# SolenoidSwitching.net
KiCad netlist of a schematic drawn in Altium Designer
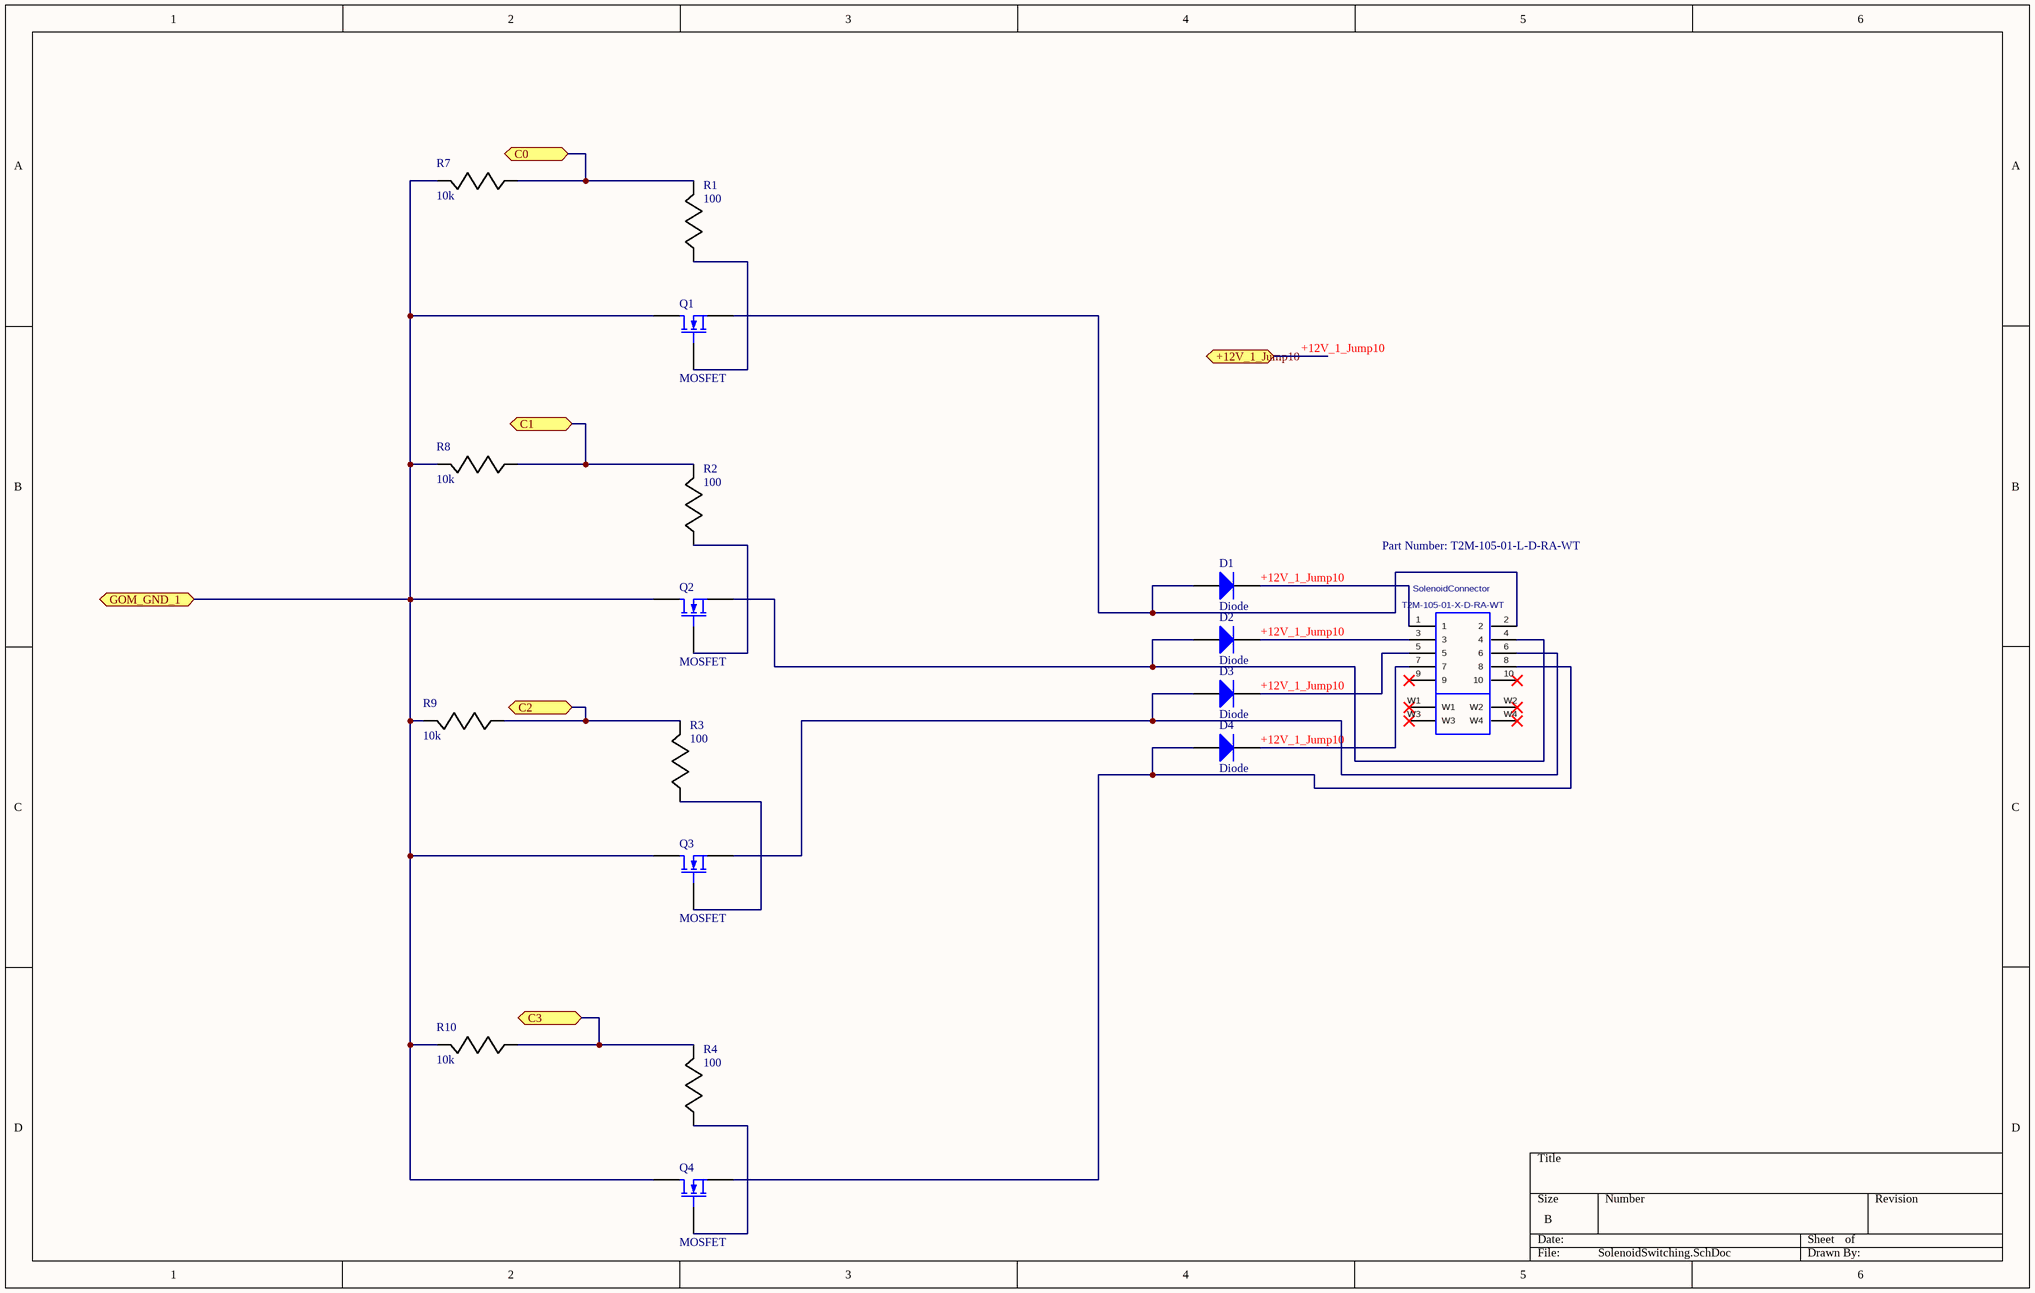
[diagram p0: SolenoidSwitching.SchDoc]

(export (version "E")
  (design (tool "Eeschema 10.0.6"))
  (components
    (comp (ref "D1")
      (value "Diode")
      (footprint "SMC")
      (description "Default Diode")
      (fields (field (name "PUBLISHER") "Altium Limited"))
      (libsource (lib "Miscellaneous Devices") (part "Diode"))
    )
    (comp (ref "D2")
      (value "Diode")
      (footprint "SMC")
      (description "Default Diode")
      (fields (field (name "PUBLISHER") "Altium Limited"))
      (libsource (lib "Miscellaneous Devices") (part "Diode"))
    )
    (comp (ref "D3")
      (value "Diode")
      (footprint "SMC")
      (description "Default Diode")
      (fields (field (name "PUBLISHER") "Altium Limited"))
      (libsource (lib "Miscellaneous Devices") (part "Diode"))
    )
    (comp (ref "D4")
      (value "Diode")
      (footprint "SMC")
      (description "Default Diode")
      (fields (field (name "PUBLISHER") "Altium Limited"))
      (libsource (lib "Miscellaneous Devices") (part "Diode"))
    )
    (comp (ref "Q1")
      (value "MOSFET")
      (footprint "TO-226-AA")
      (description "N-Channel MOSFET")
      (fields (field (name "PUBLISHER") "Altium Limited"))
      (libsource (lib "Miscellaneous Devices") (part "MOSFET-N"))
    )
    (comp (ref "Q2")
      (value "MOSFET")
      (footprint "TO-226-AA")
      (description "N-Channel MOSFET")
      (fields (field (name "PUBLISHER") "Altium Limited"))
      (libsource (lib "Miscellaneous Devices") (part "MOSFET-N"))
    )
    (comp (ref "Q3")
      (value "MOSFET")
      (footprint "TO-226-AA")
      (description "N-Channel MOSFET")
      (fields (field (name "PUBLISHER") "Altium Limited"))
      (libsource (lib "Miscellaneous Devices") (part "MOSFET-N"))
    )
    (comp (ref "Q4")
      (value "MOSFET")
      (footprint "TO-226-AA")
      (description "N-Channel MOSFET")
      (fields (field (name "PUBLISHER") "Altium Limited"))
      (libsource (lib "Miscellaneous Devices") (part "MOSFET-N"))
    )
    (comp (ref "R1")
      (value "100")
      (footprint "AXIAL-0.3")
      (description "Imported")
      (fields (field (name "MANUFACTURER_PART_NUMBER") "PMR100HZPFU6L00"))
      (libsource (lib "2016-03-26_18-23-46") (part "PMR100HZPFU6L00"))
    )
    (comp (ref "R2")
      (value "100")
      (footprint "AXIAL-0.3")
      (description "Imported")
      (fields (field (name "MANUFACTURER_PART_NUMBER") "PMR100HZPFU6L00"))
      (libsource (lib "2016-03-26_18-23-46") (part "PMR100HZPFU6L00"))
    )
    (comp (ref "R3")
      (value "100")
      (footprint "AXIAL-0.3")
      (description "Imported")
      (fields (field (name "MANUFACTURER_PART_NUMBER") "PMR100HZPFU6L00"))
      (libsource (lib "2016-03-26_18-23-46") (part "PMR100HZPFU6L00"))
    )
    (comp (ref "R4")
      (value "100")
      (footprint "AXIAL-0.3")
      (description "Imported")
      (fields (field (name "MANUFACTURER_PART_NUMBER") "PMR100HZPFU6L00"))
      (libsource (lib "2016-03-26_18-23-46") (part "PMR100HZPFU6L00"))
    )
    (comp (ref "R7")
      (value "10k")
      (footprint "AXIAL-0.3")
      (description "Imported")
      (fields (field (name "MANUFACTURER_PART_NUMBER") "PMR100HZPFU6L00"))
      (libsource (lib "2016-03-26_18-23-46") (part "PMR100HZPFU6L00"))
    )
    (comp (ref "R8")
      (value "10k")
      (footprint "AXIAL-0.3")
      (description "Imported")
      (fields (field (name "MANUFACTURER_PART_NUMBER") "PMR100HZPFU6L00"))
      (libsource (lib "2016-03-26_18-23-46") (part "PMR100HZPFU6L00"))
    )
    (comp (ref "R9")
      (value "10k")
      (footprint "AXIAL-0.3")
      (description "Imported")
      (fields (field (name "MANUFACTURER_PART_NUMBER") "PMR100HZPFU6L00"))
      (libsource (lib "2016-03-26_18-23-46") (part "PMR100HZPFU6L00"))
    )
    (comp (ref "R10")
      (value "10k")
      (footprint "AXIAL-0.3")
      (description "Imported")
      (fields (field (name "MANUFACTURER_PART_NUMBER") "PMR100HZPFU6L00"))
      (libsource (lib "2016-03-26_18-23-46") (part "PMR100HZPFU6L00"))
    )
    (comp (ref "SolenoidConnector")
      (value "T2M-105-01-X-D-RA-WT")
      (footprint "T2M-105-01-X-D-RA-WT")
      (description "2MM PITCH SHROUDED RIGHT ANGLE TERMINAL STRIP.")
      (fields
        (field (name "MANUFACTURER") "SAMTEC")
        (field (name "CREATED") "September 24, 2014 - Wendy Xin")
      )
      (libsource (lib "T2M-105-01-X-D-RA-WT") (part "T2M-105-01-X-D-RA-WT"))
    )
  )
  (nets
    (net (code "1") (name "/+12V_1_Jump10") (class "Default")
      (node (ref "D1") (pin "2") (pinfunction "K_2") (pintype "passive"))
      (node (ref "D2") (pin "2") (pinfunction "K_2") (pintype "passive"))
      (node (ref "D3") (pin "2") (pinfunction "K_2") (pintype "passive"))
      (node (ref "D4") (pin "2") (pinfunction "K_2") (pintype "passive"))
      (node (ref "SolenoidConnector") (pin "1") (pinfunction "1_1") (pintype "passive"))
      (node (ref "SolenoidConnector") (pin "3") (pinfunction "3_3") (pintype "passive"))
      (node (ref "SolenoidConnector") (pin "5") (pinfunction "5_5") (pintype "passive"))
      (node (ref "SolenoidConnector") (pin "7") (pinfunction "7_7") (pintype "passive"))
    )
    (net (code "2") (name "/C0") (class "Default")
      (node (ref "R1") (pin "1") (pinfunction "1_1") (pintype "passive"))
      (node (ref "R7") (pin "2") (pinfunction "2_2") (pintype "passive"))
    )
    (net (code "3") (name "/C1") (class "Default")
      (node (ref "R2") (pin "1") (pinfunction "1_1") (pintype "passive"))
      (node (ref "R8") (pin "2") (pinfunction "2_2") (pintype "passive"))
    )
    (net (code "4") (name "/C2") (class "Default")
      (node (ref "R3") (pin "1") (pinfunction "1_1") (pintype "passive"))
      (node (ref "R9") (pin "2") (pinfunction "2_2") (pintype "passive"))
    )
    (net (code "5") (name "/C3") (class "Default")
      (node (ref "R10") (pin "2") (pinfunction "2_2") (pintype "passive"))
      (node (ref "R4") (pin "1") (pinfunction "1_1") (pintype "passive"))
    )
    (net (code "6") (name "/GOM_GND_1") (class "Default")
      (node (ref "Q1") (pin "1") (pinfunction "D_1") (pintype "passive"))
      (node (ref "Q2") (pin "1") (pinfunction "D_1") (pintype "passive"))
      (node (ref "Q3") (pin "1") (pinfunction "D_1") (pintype "passive"))
      (node (ref "Q4") (pin "1") (pinfunction "D_1") (pintype "passive"))
      (node (ref "R10") (pin "1") (pinfunction "1_1") (pintype "passive"))
      (node (ref "R7") (pin "1") (pinfunction "1_1") (pintype "passive"))
      (node (ref "R8") (pin "1") (pinfunction "1_1") (pintype "passive"))
      (node (ref "R9") (pin "1") (pinfunction "1_1") (pintype "passive"))
    )
    (net (code "7") (name "Net-(D1-A)") (class "Default")
      (node (ref "D1") (pin "1") (pinfunction "A_1") (pintype "passive"))
      (node (ref "Q1") (pin "3") (pinfunction "S_3") (pintype "passive"))
      (node (ref "SolenoidConnector") (pin "2") (pinfunction "2_2") (pintype "passive"))
    )
    (net (code "8") (name "Net-(D2-A)") (class "Default")
      (node (ref "D2") (pin "1") (pinfunction "A_1") (pintype "passive"))
      (node (ref "Q2") (pin "3") (pinfunction "S_3") (pintype "passive"))
      (node (ref "SolenoidConnector") (pin "4") (pinfunction "4_4") (pintype "passive"))
    )
    (net (code "9") (name "Net-(D3-A)") (class "Default")
      (node (ref "D3") (pin "1") (pinfunction "A_1") (pintype "passive"))
      (node (ref "Q3") (pin "3") (pinfunction "S_3") (pintype "passive"))
      (node (ref "SolenoidConnector") (pin "6") (pinfunction "6_6") (pintype "passive"))
    )
    (net (code "10") (name "Net-(D4-A)") (class "Default")
      (node (ref "D4") (pin "1") (pinfunction "A_1") (pintype "passive"))
      (node (ref "Q4") (pin "3") (pinfunction "S_3") (pintype "passive"))
      (node (ref "SolenoidConnector") (pin "8") (pinfunction "8_8") (pintype "passive"))
    )
    (net (code "11") (name "Net-(Q1-G)") (class "Default")
      (node (ref "Q1") (pin "2") (pinfunction "G_2") (pintype "passive"))
      (node (ref "R1") (pin "2") (pinfunction "2_2") (pintype "passive"))
    )
    (net (code "12") (name "Net-(Q2-G)") (class "Default")
      (node (ref "Q2") (pin "2") (pinfunction "G_2") (pintype "passive"))
      (node (ref "R2") (pin "2") (pinfunction "2_2") (pintype "passive"))
    )
    (net (code "13") (name "Net-(Q3-G)") (class "Default")
      (node (ref "Q3") (pin "2") (pinfunction "G_2") (pintype "passive"))
      (node (ref "R3") (pin "2") (pinfunction "2_2") (pintype "passive"))
    )
    (net (code "14") (name "Net-(Q4-G)") (class "Default")
      (node (ref "Q4") (pin "2") (pinfunction "G_2") (pintype "passive"))
      (node (ref "R4") (pin "2") (pinfunction "2_2") (pintype "passive"))
    )
    (net (code "15") (name "unconnected-(SolenoidConnector-Pad9)") (class "Default")
      (node (ref "SolenoidConnector") (pin "9") (pinfunction "9_9") (pintype "passive+no_connect"))
    )
    (net (code "16") (name "unconnected-(SolenoidConnector-Pad10)") (class "Default")
      (node (ref "SolenoidConnector") (pin "10") (pinfunction "10_10") (pintype "passive+no_connect"))
    )
    (net (code "17") (name "unconnected-(SolenoidConnector-PadW1)") (class "Default")
      (node (ref "SolenoidConnector") (pin "W1") (pinfunction "W1_W1") (pintype "passive+no_connect"))
    )
    (net (code "18") (name "unconnected-(SolenoidConnector-PadW2)") (class "Default")
      (node (ref "SolenoidConnector") (pin "W2") (pinfunction "W2_W2") (pintype "passive+no_connect"))
    )
    (net (code "19") (name "unconnected-(SolenoidConnector-PadW3)") (class "Default")
      (node (ref "SolenoidConnector") (pin "W3") (pinfunction "W3_W3") (pintype "passive+no_connect"))
    )
    (net (code "20") (name "unconnected-(SolenoidConnector-PadW4)") (class "Default")
      (node (ref "SolenoidConnector") (pin "W4") (pinfunction "W4_W4") (pintype "passive+no_connect"))
    )
  )
)
